# Gate_Driver_2.net
KiCad netlist of a schematic drawn in Altium Designer
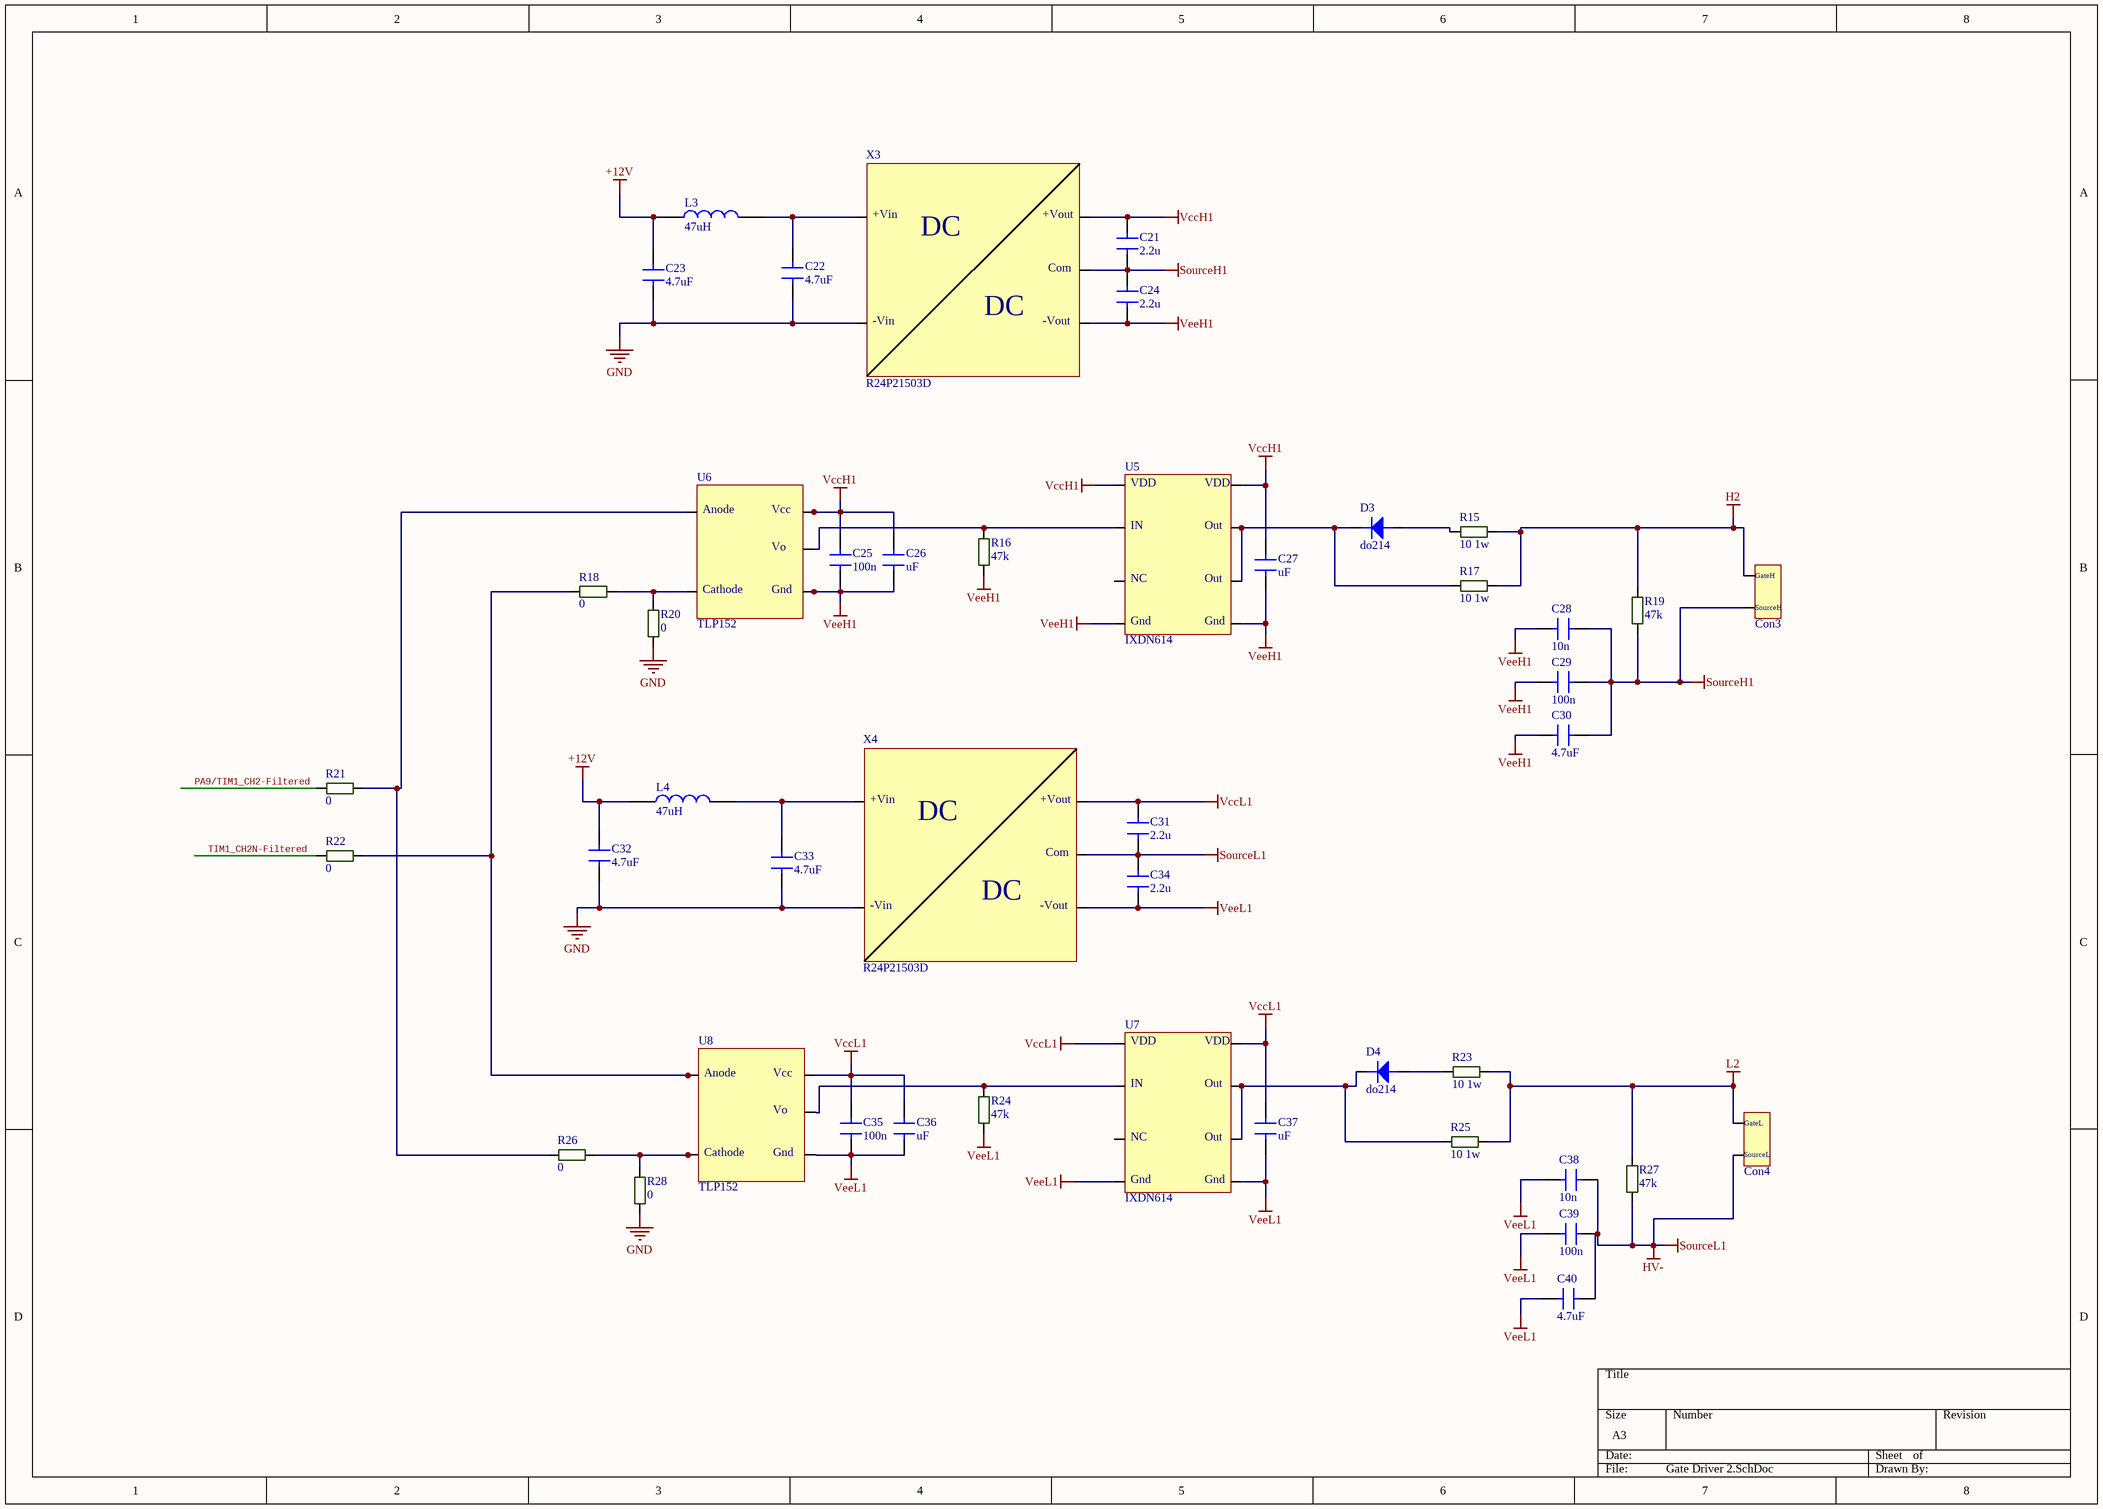
[diagram p0: Gate Driver 2.SchDoc]

(export (version "E")
  (design (tool "Eeschema 10.0.6"))
  (components
    (comp (ref "C21")
      (value "2.2u")
      (footprint "C-0805")
      (libsource (lib "Gate Driver Board") (part "C-0805"))
    )
    (comp (ref "C22")
      (value "4.7uF")
      (footprint "C-1206")
      (description "MLCC (3216) 1206 4.7uF 50VDC ±10% X7R")
      (fields (field (name "ÖZDISAN PART NUMBER") "CL31B475KBHNNNE") (field (name "MANUFACTURER") "SAMSUNG"))
      (libsource (lib "Gate Driver Board") (part "Cap1206"))
    )
    (comp (ref "C23")
      (value "4.7uF")
      (footprint "C-1206")
      (description "MLCC (3216) 1206 4.7uF 50VDC ±10% X7R")
      (fields (field (name "ÖZDISAN PART NUMBER") "CL31B475KBHNNNE") (field (name "MANUFACTURER") "SAMSUNG"))
      (libsource (lib "Gate Driver Board") (part "Cap1206"))
    )
    (comp (ref "C24")
      (value "2.2u")
      (footprint "C-0805")
      (libsource (lib "Gate Driver Board") (part "C-0805"))
    )
    (comp (ref "C25")
      (value "100n")
      (footprint "C-0805")
      (libsource (lib "Gate Driver Board") (part "C-0805"))
    )
    (comp (ref "C26") (value "uF") (footprint "C-1206") (libsource (lib "Gate Driver Board") (part "C-1206")))
    (comp (ref "C27") (value "uF") (footprint "C-1206") (libsource (lib "Gate Driver Board") (part "C-1206")))
    (comp (ref "C28")
      (value "10n")
      (footprint "C-0805")
      (libsource (lib "Gate Driver Board") (part "C-0805"))
    )
    (comp (ref "C29")
      (value "100n")
      (footprint "C-0805")
      (libsource (lib "Gate Driver Board") (part "C-0805"))
    )
    (comp (ref "C30")
      (value "4.7uF")
      (footprint "C-1206")
      (description "MLCC (3216) 1206 4.7uF 50VDC ±10% X7R")
      (fields (field (name "ÖZDISAN PART NUMBER") " CL31B475KBHNNNE") (field (name "MANUFACTURER") "SAMSUNG"))
      (libsource (lib "Gate Driver Board") (part "Cap1206"))
    )
    (comp (ref "C31")
      (value "2.2u")
      (footprint "C-0805")
      (libsource (lib "Gate Driver Board") (part "C-0805"))
    )
    (comp (ref "C32")
      (value "4.7uF")
      (footprint "C-1206")
      (description "MLCC (3216) 1206 4.7uF 50VDC ±10% X7R")
      (fields (field (name "ÖZDISAN PART NUMBER") "CL31B475KBHNNNE") (field (name "MANUFACTURER") "SAMSUNG"))
      (libsource (lib "Gate Driver Board") (part "Cap1206"))
    )
    (comp (ref "C33")
      (value "4.7uF")
      (footprint "C-1206")
      (description "MLCC (3216) 1206 4.7uF 50VDC ±10% X7R")
      (fields (field (name "ÖZDISAN PART NUMBER") " CL31B475KBHNNNE") (field (name "MANUFACTURER") "SAMSUNG"))
      (libsource (lib "Gate Driver Board") (part "Cap1206"))
    )
    (comp (ref "C34")
      (value "2.2u")
      (footprint "C-0805")
      (libsource (lib "Gate Driver Board") (part "C-0805"))
    )
    (comp (ref "C35")
      (value "100n")
      (footprint "C-0805")
      (libsource (lib "Gate Driver Board") (part "C-0805"))
    )
    (comp (ref "C36") (value "uF") (footprint "C-1206") (libsource (lib "Gate Driver Board") (part "C-1206")))
    (comp (ref "C37") (value "uF") (footprint "C-1206") (libsource (lib "Gate Driver Board") (part "C-1206")))
    (comp (ref "C38")
      (value "10n")
      (footprint "C-0805")
      (libsource (lib "Gate Driver Board") (part "C-0805"))
    )
    (comp (ref "C39")
      (value "100n")
      (footprint "C-0805")
      (libsource (lib "Gate Driver Board") (part "C-0805"))
    )
    (comp (ref "C40")
      (value "4.7uF")
      (footprint "C-1206")
      (description "MLCC (3216) 1206 4.7uF 50VDC ±10% X7R")
      (fields (field (name "ÖZDISAN PART NUMBER") "CL31B475KBHNNNE") (field (name "MANUFACTURER") "SAMSUNG"))
      (libsource (lib "Gate Driver Board") (part "Cap1206"))
    )
    (comp (ref "Con3")
      (value "Connector2_1")
      (footprint "Conn")
      (libsource (lib "Gate Driver Board") (part "Connector2_1"))
    )
    (comp (ref "Con4")
      (value "Connector2_2")
      (footprint "Conn")
      (libsource (lib "Gate Driver Board") (part "Connector2_2"))
    )
    (comp (ref "D3")
      (value "do214")
      (footprint "DO-214AC")
      (description "DIODE FAST SWITCHING Single 150mA 75V SMT SOD323")
      (libsource (lib "Gate Driver Board") (part "do214"))
    )
    (comp (ref "D4")
      (value "do214")
      (footprint "DO-214AC")
      (description "DIODE FAST SWITCHING Single 150mA 75V SMT SOD323")
      (libsource (lib "Gate Driver Board") (part "do214"))
    )
    (comp (ref "L3")
      (value "47uH")
      (footprint "WE-TPC_282892")
      (libsource (lib "Gate Driver Board") (part "inductor"))
    )
    (comp (ref "L4")
      (value "47uH")
      (footprint "WE-TPC_282892")
      (libsource (lib "Gate Driver Board") (part "inductor"))
    )
    (comp (ref "R15")
      (value "10 1w")
      (footprint "R-2512")
      (libsource (lib "Gate Driver Board") (part "R-2512"))
    )
    (comp (ref "R16")
      (value "47k")
      (footprint "R-0805")
      (description "RES.(2012) 0805 47K Ohms 5% 1/8W-S 100PPM")
      (fields (field (name "MANUFACTURER") "ROYALOHM") (field (name "ÖZDISAN PART NUMBER") "0805S8J0473T5E"))
      (libsource (lib "Gate Driver Board") (part "Res0805"))
    )
    (comp (ref "R17")
      (value "10 1w")
      (footprint "R-2512")
      (libsource (lib "Gate Driver Board") (part "R-2512"))
    )
    (comp (ref "R18")
      (value "0")
      (footprint "R-0805")
      (description "RES.(2012) 0805 0 Ohms 5% 1/8W-S 800PPM")
      (fields (field (name "MANUFACTURER") "ROYALOHM") (field (name "ÖZDISAN PART NUMBER") "0805S8J0000T5E"))
      (libsource (lib "Gate Driver Board") (part "Res0805"))
    )
    (comp (ref "R19")
      (value "47k")
      (footprint "R-0805")
      (description "RES.(2012) 0805 47K Ohms 5% 1/8W-S 100PPM")
      (fields (field (name "ÖZDISAN PART NUMBER") "0805S8J0473T5E") (field (name "MANUFACTURER") "ROYALOHM"))
      (libsource (lib "Gate Driver Board") (part "Res0805"))
    )
    (comp (ref "R20")
      (value "0")
      (footprint "R-0805")
      (description "RES.(2012) 0805 0 Ohms 5% 1/8W-S 800PPM")
      (fields (field (name "MANUFACTURER") "ROYALOHM") (field (name "ÖZDISAN PART NUMBER") "0805S8J0000T5E"))
      (libsource (lib "Gate Driver Board") (part "Res0805"))
    )
    (comp (ref "R21")
      (value "0")
      (footprint "R-0805")
      (description "RES.(2012) 0805 0 Ohms 5% 1/8W-S 800PPM")
      (fields (field (name "MANUFACTURER") "ROYALOHM") (field (name "ÖZDISAN PART NUMBER") "0805S8J0000T5E"))
      (libsource (lib "Gate Driver Board") (part "Res0805"))
    )
    (comp (ref "R22")
      (value "0")
      (footprint "R-0805")
      (description "RES.(2012) 0805 0 Ohms 5% 1/8W-S 800PPM")
      (fields (field (name "MANUFACTURER") "ROYALOHM") (field (name "ÖZDISAN PART NUMBER") "0805S8J0000T5E"))
      (libsource (lib "Gate Driver Board") (part "Res0805"))
    )
    (comp (ref "R23")
      (value "10 1w")
      (footprint "R-2512")
      (libsource (lib "Gate Driver Board") (part "R-2512"))
    )
    (comp (ref "R24")
      (value "47k")
      (footprint "R-0805")
      (description "RES.(2012) 0805 47K Ohms 5% 1/8W-S 100PPM")
      (fields (field (name "ÖZDISAN PART NUMBER") "0805S8J0473T5E") (field (name "MANUFACTURER") "ROYALOHM"))
      (libsource (lib "Gate Driver Board") (part "Res0805"))
    )
    (comp (ref "R25")
      (value "10 1w")
      (footprint "R-2512")
      (libsource (lib "Gate Driver Board") (part "R-2512"))
    )
    (comp (ref "R26")
      (value "0")
      (footprint "R-0805")
      (description "RES.(2012) 0805 0 Ohms 5% 1/8W-S 800PPM")
      (fields (field (name "MANUFACTURER") "ROYALOHM") (field (name "ÖZDISAN PART NUMBER") "0805S8J0000T5E"))
      (libsource (lib "Gate Driver Board") (part "Res0805"))
    )
    (comp (ref "R27")
      (value "47k")
      (footprint "R-0805")
      (description "RES.(2012) 0805 47K Ohms 5% 1/8W-S 100PPM")
      (fields (field (name "ÖZDISAN PART NUMBER") "0805S8J0473T5E") (field (name "MANUFACTURER") "ROYALOHM"))
      (libsource (lib "Gate Driver Board") (part "Res0805"))
    )
    (comp (ref "R28")
      (value "0")
      (footprint "R-0805")
      (description "RES.(2012) 0805 0 Ohms 5% 1/8W-S 800PPM")
      (fields (field (name "MANUFACTURER") "ROYALOHM") (field (name "ÖZDISAN PART NUMBER") "0805S8J0000T5E"))
      (libsource (lib "Gate Driver Board") (part "Res0805"))
    )
    (comp (ref "U5")
      (value "IXDN614")
      (footprint "FAN3122 Soic8")
      (description "14A 8SOIC EXP MTL NON INVERTING")
      (fields
        (field (name "MANUFACTURER") "Ixys Clare")
        (field (name "MANUFACTURER PART NUMBER") "IXDN614SITR")
      )
      (libsource (lib "Gate Driver Board") (part "IXDN614SITR"))
    )
    (comp (ref "U6")
      (value "TLP152")
      (footprint "TLP152")
      (description "OPTOISO 3.75KV GATE DRIVER 6SO-5")
      (fields
        (field (name "MANUFACTURER") "Toshiba")
        (field (name "MANUFACTURER PART NUMBER") "TLP152(TPL,E")
      )
      (libsource (lib "Gate Driver Board") (part "TLP152(TPL,E"))
    )
    (comp (ref "U7")
      (value "IXDN614")
      (footprint "FAN3122 Soic8")
      (description "14A 8SOIC EXP MTL NON INVERTING")
      (fields
        (field (name "MANUFACTURER") "Ixys Clare")
        (field (name "MANUFACTURER PART NUMBER") "IXDN614SITR")
      )
      (libsource (lib "Gate Driver Board") (part "IXDN614SITR"))
    )
    (comp (ref "U8")
      (value "TLP152")
      (footprint "TLP152")
      (description "OPTOISO 3.75KV GATE DRIVER 6SO-5")
      (fields
        (field (name "MANUFACTURER") "Toshiba")
        (field (name "MANUFACTURER PART NUMBER") "TLP152(TPL,E")
      )
      (libsource (lib "Gate Driver Board") (part "TLP152(TPL,E"))
    )
    (comp (ref "X3")
      (value "R24P21503D")
      (footprint "SIP7")
      (fields (field (name "MANUFACTURER") "Recom"))
      (libsource (lib "Gate Driver Board") (part "R24P21503D"))
    )
    (comp (ref "X4")
      (value "R24P21503D")
      (footprint "SIP7")
      (fields (field (name "MANUFACTURER") "Recom"))
      (libsource (lib "Gate Driver Board") (part "R24P21503D"))
    )
  )
  (nets
    (net (code "1") (name "+12V") (class "Default")
      (node (ref "C23") (pin "2") (pinfunction "2_2") (pintype "passive"))
      (node (ref "C32") (pin "2") (pinfunction "2_2") (pintype "passive"))
      (node (ref "L3") (pin "1") (pinfunction "1_1") (pintype "passive"))
      (node (ref "L4") (pin "1") (pinfunction "1_1") (pintype "passive"))
    )
    (net (code "2") (name "/PA9{slash}TIM1_CH2-Filtered") (class "Default")
      (node (ref "R21") (pin "1") (pinfunction "1_1") (pintype "passive"))
    )
    (net (code "3") (name "/TIM1_CH2N-Filtered") (class "Default")
      (node (ref "R22") (pin "1") (pinfunction "1_1") (pintype "passive"))
    )
    (net (code "4") (name "GND") (class "Default")
      (node (ref "C22") (pin "1") (pinfunction "1_1") (pintype "passive"))
      (node (ref "C23") (pin "1") (pinfunction "1_1") (pintype "passive"))
      (node (ref "C32") (pin "1") (pinfunction "1_1") (pintype "passive"))
      (node (ref "C33") (pin "1") (pinfunction "1_1") (pintype "passive"))
      (node (ref "R20") (pin "1") (pinfunction "1_1") (pintype "passive"))
      (node (ref "R28") (pin "1") (pinfunction "1_1") (pintype "passive"))
      (node (ref "X3") (pin "2") (pinfunction "2_2") (pintype "passive"))
      (node (ref "X4") (pin "2") (pinfunction "2_2") (pintype "passive"))
    )
    (net (code "5") (name "H2") (class "Default")
      (node (ref "Con3") (pin "1") (pinfunction "1_1") (pintype "passive"))
      (node (ref "R15") (pin "2") (pinfunction "2_2") (pintype "passive"))
      (node (ref "R17") (pin "2") (pinfunction "2_2") (pintype "passive"))
      (node (ref "R19") (pin "2") (pinfunction "2_2") (pintype "passive"))
    )
    (net (code "6") (name "HV-") (class "Default")
      (node (ref "C31") (pin "1") (pinfunction "1_1") (pintype "passive"))
      (node (ref "C34") (pin "2") (pinfunction "2_2") (pintype "passive"))
      (node (ref "C38") (pin "1") (pinfunction "1_1") (pintype "passive"))
      (node (ref "C39") (pin "1") (pinfunction "1_1") (pintype "passive"))
      (node (ref "C40") (pin "2") (pinfunction "2_2") (pintype "passive"))
      (node (ref "Con4") (pin "2") (pinfunction "2_2") (pintype "passive"))
      (node (ref "R27") (pin "1") (pinfunction "1_1") (pintype "passive"))
      (node (ref "X4") (pin "6") (pinfunction "6_6") (pintype "passive"))
    )
    (net (code "7") (name "L2") (class "Default")
      (node (ref "Con4") (pin "1") (pinfunction "1_1") (pintype "passive"))
      (node (ref "R23") (pin "2") (pinfunction "2_2") (pintype "passive"))
      (node (ref "R25") (pin "2") (pinfunction "2_2") (pintype "passive"))
      (node (ref "R27") (pin "2") (pinfunction "2_2") (pintype "passive"))
    )
    (net (code "8") (name "Net-(C22-Pad2)") (class "Default")
      (node (ref "C22") (pin "2") (pinfunction "2_2") (pintype "passive"))
      (node (ref "L3") (pin "2") (pinfunction "2_2") (pintype "passive"))
      (node (ref "X3") (pin "1") (pinfunction "1_1") (pintype "passive"))
    )
    (net (code "9") (name "Net-(C33-Pad2)") (class "Default")
      (node (ref "C33") (pin "2") (pinfunction "2_2") (pintype "passive"))
      (node (ref "L4") (pin "2") (pinfunction "2_2") (pintype "passive"))
      (node (ref "X4") (pin "1") (pinfunction "1_1") (pintype "passive"))
    )
    (net (code "10") (name "Net-(D3-Pada)") (class "Default")
      (node (ref "D3") (pin "a") (pinfunction "a_a") (pintype "passive"))
      (node (ref "R15") (pin "1") (pinfunction "1_1") (pintype "passive"))
    )
    (net (code "11") (name "Net-(D3-Padk)") (class "Default")
      (node (ref "D3") (pin "k") (pinfunction "k_k") (pintype "passive"))
      (node (ref "R17") (pin "1") (pinfunction "1_1") (pintype "passive"))
      (node (ref "U5") (pin "6") (pinfunction "6_6") (pintype "passive"))
      (node (ref "U5") (pin "7") (pinfunction "7_7") (pintype "passive"))
    )
    (net (code "12") (name "Net-(D4-Pada)") (class "Default")
      (node (ref "D4") (pin "a") (pinfunction "a_a") (pintype "passive"))
      (node (ref "R23") (pin "1") (pinfunction "1_1") (pintype "passive"))
    )
    (net (code "13") (name "Net-(D4-Padk)") (class "Default")
      (node (ref "D4") (pin "k") (pinfunction "k_k") (pintype "passive"))
      (node (ref "R25") (pin "1") (pinfunction "1_1") (pintype "passive"))
      (node (ref "U7") (pin "6") (pinfunction "6_6") (pintype "passive"))
      (node (ref "U7") (pin "7") (pinfunction "7_7") (pintype "passive"))
    )
    (net (code "14") (name "Net-(R16-Pad2)") (class "Default")
      (node (ref "R16") (pin "2") (pinfunction "2_2") (pintype "passive"))
      (node (ref "U5") (pin "2") (pinfunction "2_2") (pintype "passive"))
      (node (ref "U6") (pin "4") (pinfunction "4_4") (pintype "passive"))
    )
    (net (code "15") (name "Net-(R18-Pad1)") (class "Default")
      (node (ref "R18") (pin "1") (pinfunction "1_1") (pintype "passive"))
      (node (ref "R22") (pin "2") (pinfunction "2_2") (pintype "passive"))
      (node (ref "U8") (pin "1") (pinfunction "1_1") (pintype "passive"))
    )
    (net (code "16") (name "Net-(R18-Pad2)") (class "Default")
      (node (ref "R18") (pin "2") (pinfunction "2_2") (pintype "passive"))
      (node (ref "R20") (pin "2") (pinfunction "2_2") (pintype "passive"))
      (node (ref "U6") (pin "2") (pinfunction "2_2") (pintype "passive"))
    )
    (net (code "17") (name "Net-(R21-Pad2)") (class "Default")
      (node (ref "R21") (pin "2") (pinfunction "2_2") (pintype "passive"))
      (node (ref "R26") (pin "1") (pinfunction "1_1") (pintype "passive"))
      (node (ref "U6") (pin "1") (pinfunction "1_1") (pintype "passive"))
    )
    (net (code "18") (name "Net-(R24-Pad2)") (class "Default")
      (node (ref "R24") (pin "2") (pinfunction "2_2") (pintype "passive"))
      (node (ref "U7") (pin "2") (pinfunction "2_2") (pintype "passive"))
      (node (ref "U8") (pin "4") (pinfunction "4_4") (pintype "passive"))
    )
    (net (code "19") (name "Net-(R26-Pad2)") (class "Default")
      (node (ref "R26") (pin "2") (pinfunction "2_2") (pintype "passive"))
      (node (ref "R28") (pin "2") (pinfunction "2_2") (pintype "passive"))
      (node (ref "U8") (pin "2") (pinfunction "2_2") (pintype "passive"))
    )
    (net (code "20") (name "SourceH1") (class "Default")
      (node (ref "C21") (pin "1") (pinfunction "1_1") (pintype "passive"))
      (node (ref "C24") (pin "2") (pinfunction "2_2") (pintype "passive"))
      (node (ref "C28") (pin "1") (pinfunction "1_1") (pintype "passive"))
      (node (ref "C29") (pin "1") (pinfunction "1_1") (pintype "passive"))
      (node (ref "C30") (pin "2") (pinfunction "2_2") (pintype "passive"))
      (node (ref "Con3") (pin "2") (pinfunction "2_2") (pintype "passive"))
      (node (ref "R19") (pin "1") (pinfunction "1_1") (pintype "passive"))
      (node (ref "X3") (pin "6") (pinfunction "6_6") (pintype "passive"))
    )
    (net (code "21") (name "VccH1") (class "Default")
      (node (ref "C21") (pin "2") (pinfunction "2_2") (pintype "passive"))
      (node (ref "C25") (pin "2") (pinfunction "2_2") (pintype "passive"))
      (node (ref "C26") (pin "2") (pinfunction "2_2") (pintype "passive"))
      (node (ref "C27") (pin "2") (pinfunction "2_2") (pintype "passive"))
      (node (ref "U5") (pin "1") (pinfunction "1_1") (pintype "passive"))
      (node (ref "U5") (pin "8") (pinfunction "8_8") (pintype "passive"))
      (node (ref "U6") (pin "5") (pinfunction "5_5") (pintype "passive"))
      (node (ref "X3") (pin "7") (pinfunction "7_7") (pintype "passive"))
    )
    (net (code "22") (name "VccL1") (class "Default")
      (node (ref "C31") (pin "2") (pinfunction "2_2") (pintype "passive"))
      (node (ref "C35") (pin "2") (pinfunction "2_2") (pintype "passive"))
      (node (ref "C36") (pin "2") (pinfunction "2_2") (pintype "passive"))
      (node (ref "C37") (pin "2") (pinfunction "2_2") (pintype "passive"))
      (node (ref "U7") (pin "1") (pinfunction "1_1") (pintype "passive"))
      (node (ref "U7") (pin "8") (pinfunction "8_8") (pintype "passive"))
      (node (ref "U8") (pin "5") (pinfunction "5_5") (pintype "passive"))
      (node (ref "X4") (pin "7") (pinfunction "7_7") (pintype "passive"))
    )
    (net (code "23") (name "VeeH1") (class "Default")
      (node (ref "C24") (pin "1") (pinfunction "1_1") (pintype "passive"))
      (node (ref "C25") (pin "1") (pinfunction "1_1") (pintype "passive"))
      (node (ref "C26") (pin "1") (pinfunction "1_1") (pintype "passive"))
      (node (ref "C27") (pin "1") (pinfunction "1_1") (pintype "passive"))
      (node (ref "C28") (pin "2") (pinfunction "2_2") (pintype "passive"))
      (node (ref "C29") (pin "2") (pinfunction "2_2") (pintype "passive"))
      (node (ref "C30") (pin "1") (pinfunction "1_1") (pintype "passive"))
      (node (ref "R16") (pin "1") (pinfunction "1_1") (pintype "passive"))
      (node (ref "U5") (pin "4") (pinfunction "4_4") (pintype "passive"))
      (node (ref "U5") (pin "5") (pinfunction "5_5") (pintype "passive"))
      (node (ref "U6") (pin "3") (pinfunction "3_3") (pintype "passive"))
      (node (ref "X3") (pin "5") (pinfunction "5_5") (pintype "passive"))
    )
    (net (code "24") (name "VeeL1") (class "Default")
      (node (ref "C34") (pin "1") (pinfunction "1_1") (pintype "passive"))
      (node (ref "C35") (pin "1") (pinfunction "1_1") (pintype "passive"))
      (node (ref "C36") (pin "1") (pinfunction "1_1") (pintype "passive"))
      (node (ref "C37") (pin "1") (pinfunction "1_1") (pintype "passive"))
      (node (ref "C38") (pin "2") (pinfunction "2_2") (pintype "passive"))
      (node (ref "C39") (pin "2") (pinfunction "2_2") (pintype "passive"))
      (node (ref "C40") (pin "1") (pinfunction "1_1") (pintype "passive"))
      (node (ref "R24") (pin "1") (pinfunction "1_1") (pintype "passive"))
      (node (ref "U7") (pin "4") (pinfunction "4_4") (pintype "passive"))
      (node (ref "U7") (pin "5") (pinfunction "5_5") (pintype "passive"))
      (node (ref "U8") (pin "3") (pinfunction "3_3") (pintype "passive"))
      (node (ref "X4") (pin "5") (pinfunction "5_5") (pintype "passive"))
    )
    (net (code "25") (name "unconnected-(U5-Pad3)") (class "Default")
      (node (ref "U5") (pin "3") (pinfunction "3_3") (pintype "passive"))
    )
    (net (code "26") (name "unconnected-(U7-Pad3)") (class "Default")
      (node (ref "U7") (pin "3") (pinfunction "3_3") (pintype "passive"))
    )
  )
)
